# Amplifier.net
KiCad netlist of a schematic drawn in Altium Designer
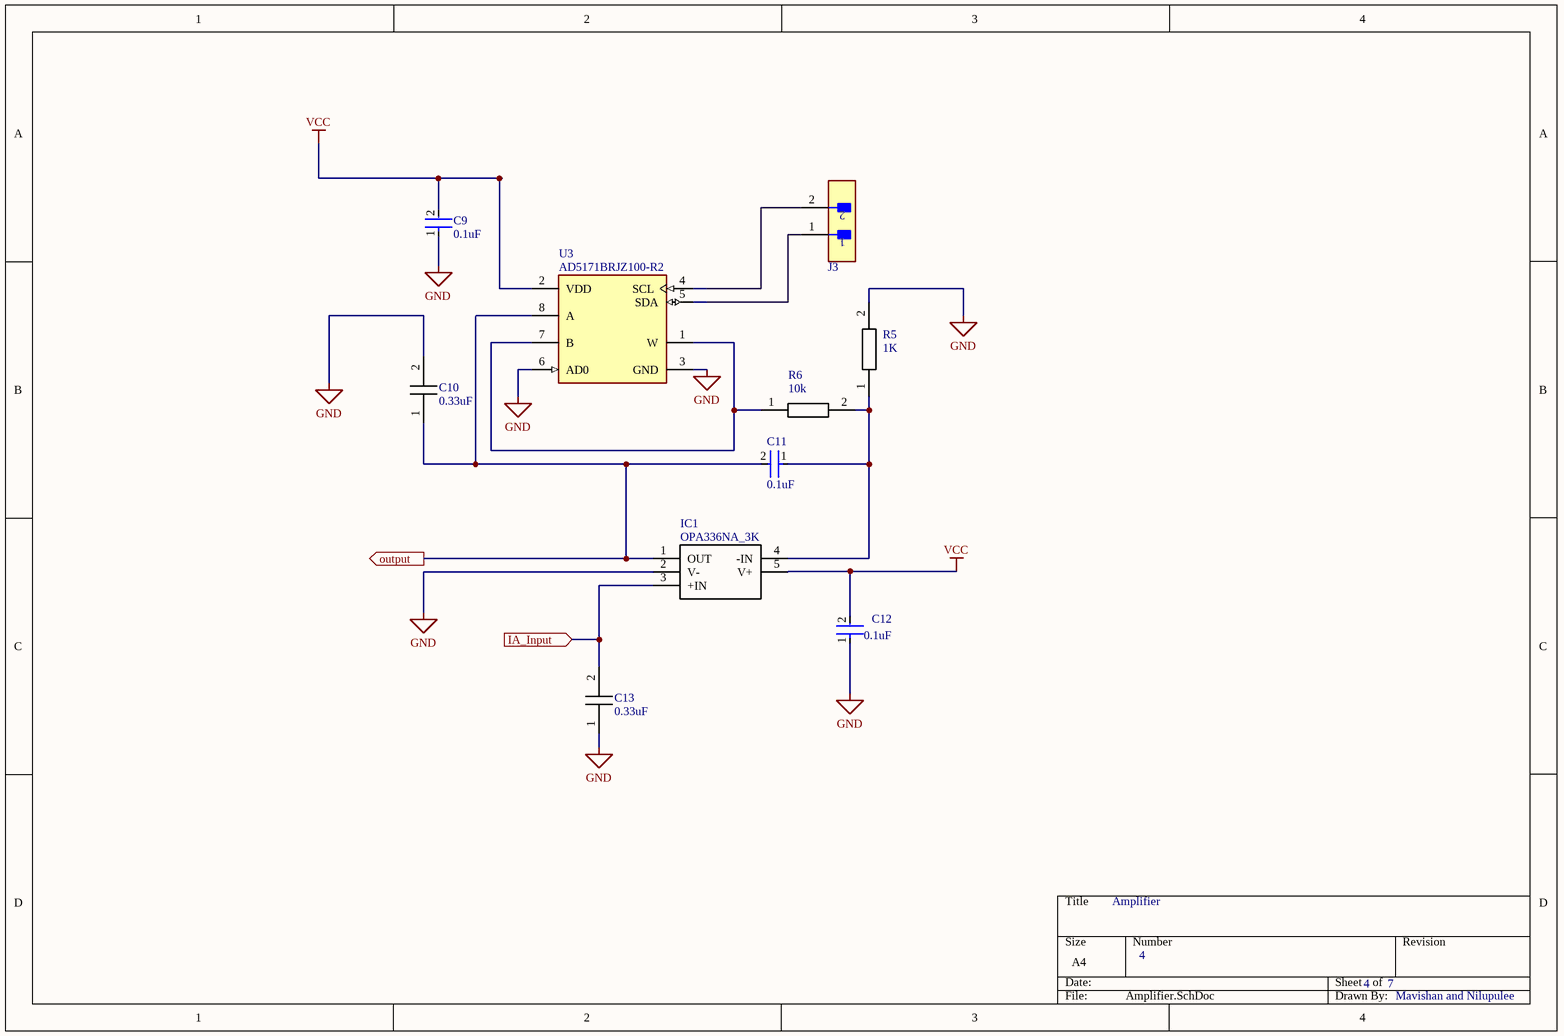
[diagram p0: Amplifier.SchDoc]

(export (version "E")
  (design (tool "Eeschema 10.0.6"))
  (components
    (comp (ref "C9")
      (value "0.1uF")
      (footprint "FP-C1206C-EB-MFG")
      (description "CAP CER 0.1UF 25V C0G/NP0 1206")
      (fields
        (field (name "MANUFACTURER") "KEMET")
        (field (name "MANUFACTURER PART NUMBER") "C1206C104F3GACTU")
      )
      (libsource (lib "Altium Content Vault") (part "b4654b650e69147ec39a6b967a45e02"))
    )
    (comp (ref "C10")
      (value "12063C334MAT2A")
      (footprint "SamacSys:CAPC3216X127N")
      (description "Capacitor")
      (fields (field (name "MOUSER PART NUMBER") "581-12063C334MAT2A") (field (name "PARAMETER 1") "0.33uF"))
      (libsource (lib "*") (part "12063C334MAT2A"))
    )
    (comp (ref "C11")
      (value "0.1uF")
      (footprint "FP-C1206C-EB-MFG")
      (description "CAP CER 0.1UF 25V C0G/NP0 1206")
      (fields
        (field (name "MANUFACTURER") "KEMET")
        (field (name "MANUFACTURER PART NUMBER") "C1206C104F3GACTU")
      )
      (libsource (lib "Altium Content Vault") (part "b4654b650e69147ec39a6b967a45e02"))
    )
    (comp (ref "C12")
      (value "0.1uF")
      (footprint "FP-C1206C-EB-MFG")
      (description "CAP CER 0.1UF 25V C0G/NP0 1206")
      (fields
        (field (name "MANUFACTURER") "KEMET")
        (field (name "MANUFACTURER PART NUMBER") "C1206C104F3GACTU")
      )
      (libsource (lib "Altium Content Vault") (part "b4654b650e69147ec39a6b967a45e02"))
    )
    (comp (ref "C13")
      (value "12063C334MAT2A")
      (footprint "SamacSys:CAPC3216X127N")
      (description "Capacitor")
      (fields (field (name "MOUSER PART NUMBER") "581-12063C334MAT2A") (field (name "PARAMETER 1") "0.33uF"))
      (libsource (lib "*") (part "12063C334MAT2A"))
    )
    (comp (ref "IC1")
      (value "OPA336NA_3K")
      (footprint "SamacSys:SOT95P280X145-5N")
      (description "Integrated Circuit")
      (fields
        (field (name "MANUFACTURER_PART_NUMBER") "OPA336NA/3K")
        (field (name "MOUSER PART NUMBER") "595-OPA336NA/3K")
      )
      (libsource (lib "*") (part "OPA336NA_3K"))
    )
    (comp (ref "J3")
      (value "M20-9990246")
      (footprint "FP-M20-9990246-MFG")
      (description "CONN HEADER VERT 2POS 2.54MM")
      (fields
        (field (name "OCTOPART") "https://octopart.com/m20-9990246-harwin-2590635")
        (field (name "MANUFACTURER") "Harwin")
      )
      (libsource (lib "Altium Content Vault") (part "3bc925449376181038e59eaffc5286c"))
    )
    (comp (ref "R5")
      (value "ERA8AEB102V")
      (footprint "SamacSys:RESC3216X70N")
      (description "Resistor")
      (fields (field (name "PARAMETER 1") "1K"))
      (libsource (lib "*") (part "ERA8AEB102V"))
    )
    (comp (ref "R6")
      (value "ERA-8AEB103V")
      (footprint "SamacSys:RESC3216X70N")
      (description "Resistor")
      (fields (field (name "MOUSER PART NUMBER") "667-ERA-8AEB103V") (field (name "PARAMETER 1") "10k"))
      (libsource (lib "SamacSys") (part "ERA-8AEB103V"))
    )
    (comp (ref "U3")
      (value "AD5171BRJZ100-R2")
      (footprint "FP-RJ-8-IPC_A")
      (description "AD5171BRJZ100-R2 Digital Potentiometer 64POS 100kOhm Single Automotive 8-Pin SOT-23 T/R")
      (fields (field (name "TOLERANCE") "30%"))
      (libsource (lib "Altium Content Vault") (part "b7c56c75a673f54426577c74fe16793"))
    )
  )
  (nets
    (net (code "1") (name "/IA_Input") (class "Default")
      (node (ref "C13") (pin "2") (pinfunction "C2_2") (pintype "passive"))
      (node (ref "IC1") (pin "3") (pinfunction "+IN_3") (pintype "passive"))
    )
    (net (code "2") (name "/output") (class "Default")
      (node (ref "C10") (pin "1") (pinfunction "C1_1") (pintype "passive"))
      (node (ref "C11") (pin "2") (pinfunction "2_2") (pintype "passive"))
      (node (ref "IC1") (pin "1") (pinfunction "OUT_1") (pintype "passive"))
      (node (ref "U3") (pin "8") (pinfunction "A_8") (pintype "passive"))
    )
    (net (code "3") (name "GND") (class "Default")
      (node (ref "C10") (pin "2") (pinfunction "C2_2") (pintype "passive"))
      (node (ref "C12") (pin "1") (pinfunction "1_1") (pintype "passive"))
      (node (ref "C13") (pin "1") (pinfunction "C1_1") (pintype "passive"))
      (node (ref "C9") (pin "1") (pinfunction "1_1") (pintype "passive"))
      (node (ref "IC1") (pin "2") (pinfunction "V-_2") (pintype "passive"))
      (node (ref "R5") (pin "2") (pinfunction "2_2") (pintype "passive"))
      (node (ref "U3") (pin "3") (pinfunction "GND_3") (pintype "power_in"))
      (node (ref "U3") (pin "6") (pinfunction "AD0_6") (pintype "input"))
    )
    (net (code "4") (name "Net-(IC1--IN)") (class "Default")
      (node (ref "C11") (pin "1") (pinfunction "1_1") (pintype "passive"))
      (node (ref "IC1") (pin "4") (pinfunction "-IN_4") (pintype "passive"))
      (node (ref "R5") (pin "1") (pinfunction "1_1") (pintype "passive"))
      (node (ref "R6") (pin "2") (pinfunction "2_2") (pintype "passive"))
    )
    (net (code "5") (name "Net-(U3-B)") (class "Default")
      (node (ref "R6") (pin "1") (pinfunction "1_1") (pintype "passive"))
      (node (ref "U3") (pin "1") (pinfunction "W_1") (pintype "passive"))
      (node (ref "U3") (pin "7") (pinfunction "B_7") (pintype "passive"))
    )
    (net (code "6") (name "Net-(U3-SCL)") (class "Default")
      (node (ref "J3") (pin "2") (pinfunction "2_2") (pintype "passive"))
      (node (ref "U3") (pin "4") (pinfunction "SCL_4") (pintype "input"))
    )
    (net (code "7") (name "Net-(U3-SDA)") (class "Default")
      (node (ref "J3") (pin "1") (pinfunction "1_1") (pintype "passive"))
      (node (ref "U3") (pin "5") (pinfunction "SDA_5") (pintype "bidirectional"))
    )
    (net (code "8") (name "VCC") (class "Default")
      (node (ref "C12") (pin "2") (pinfunction "2_2") (pintype "passive"))
      (node (ref "C9") (pin "2") (pinfunction "2_2") (pintype "passive"))
      (node (ref "IC1") (pin "5") (pinfunction "V+_5") (pintype "passive"))
      (node (ref "U3") (pin "2") (pinfunction "VDD_2") (pintype "power_in"))
    )
  )
)
